# Microcontroller_board_Photodiode_plate.net
KiCad netlist of a schematic drawn in EasyEDA
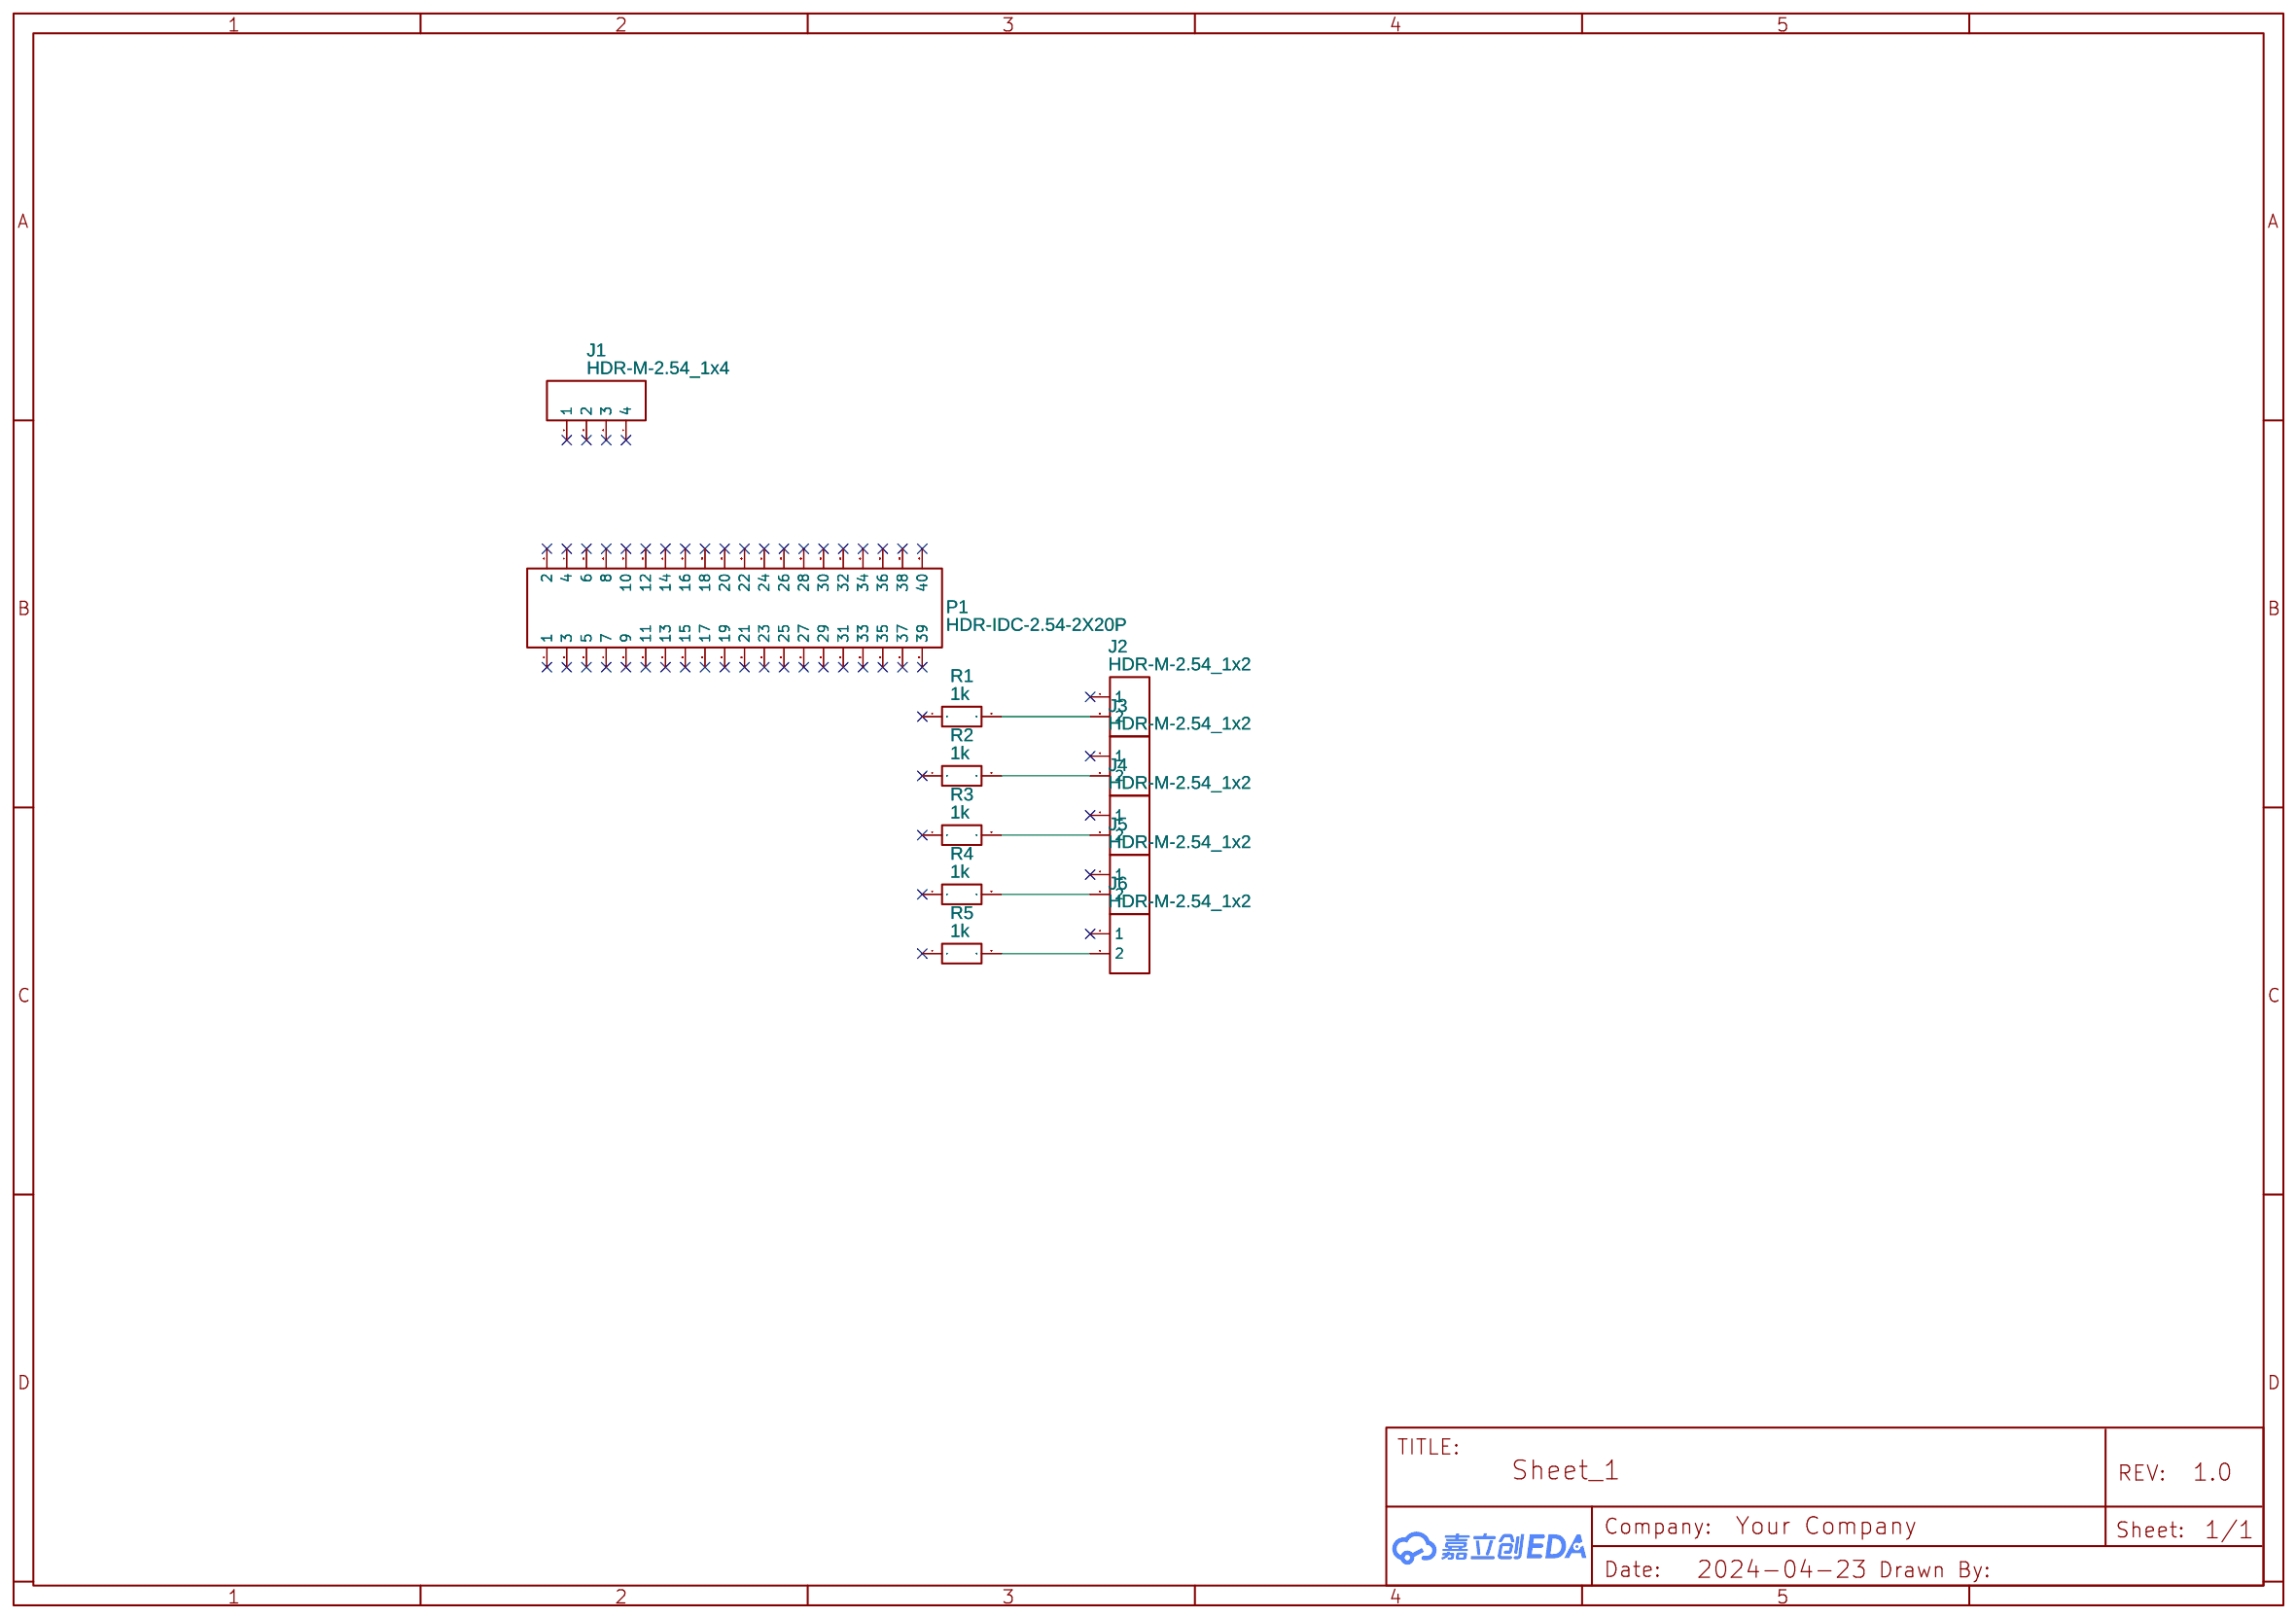
[diagram p0: schematic sheet]

(export (version "E")
  (design (tool "Eeschema 10.0.6"))
  (components
    (comp (ref "J1")
      (value "HDR-M-2.54_1x4")
      (fields (field (name "BOM_Supplier Part") "C124378"))
      (libsource (lib "") (part "HDR-M-2.54_1x4"))
    )
    (comp (ref "J2")
      (value "HDR-M-2.54_1x2")
      (fields (field (name "BOM_Supplier Part") "C124375"))
      (libsource (lib "") (part "HDR-M-2.54_1x2"))
    )
    (comp (ref "J3")
      (value "HDR-M-2.54_1x2")
      (fields (field (name "BOM_Supplier Part") "C124375"))
      (libsource (lib "") (part "HDR-M-2.54_1x2"))
    )
    (comp (ref "J4")
      (value "HDR-M-2.54_1x2")
      (fields (field (name "BOM_Supplier Part") "C124375"))
      (libsource (lib "") (part "HDR-M-2.54_1x2"))
    )
    (comp (ref "J5")
      (value "HDR-M-2.54_1x2")
      (fields (field (name "BOM_Supplier Part") "C124375"))
      (libsource (lib "") (part "HDR-M-2.54_1x2"))
    )
    (comp (ref "J6")
      (value "HDR-M-2.54_1x2")
      (fields (field (name "BOM_Supplier Part") "C124375"))
      (libsource (lib "") (part "HDR-M-2.54_1x2"))
    )
    (comp (ref "P1")
      (value "HDR-IDC-2.54-2X20P")
      (fields
        (field (name "BOM_Manufacturer Part") "IDC Box 2X20 2.54MM")
        (field (name "BOM_Supplier Part") "C9138")
      )
      (libsource (lib "") (part "HDR-IDC-2.54-2X20P"))
    )
    (comp (ref "R1") (value "1k") (libsource (lib "") (part "R_0805_EU")))
    (comp (ref "R2") (value "1k") (libsource (lib "") (part "R_0805_EU")))
    (comp (ref "R3") (value "1k") (libsource (lib "") (part "R_0805_EU")))
    (comp (ref "R4") (value "1k") (libsource (lib "") (part "R_0805_EU")))
    (comp (ref "R5") (value "1k") (libsource (lib "") (part "R_0805_EU")))
  )
  (nets
    (net (code "1") (name "Net-(J2-Pad2)") (class "Default")
      (node (ref "J2") (pin "2") (pinfunction "2_2") (pintype "unspecified"))
      (node (ref "R1") (pin "2") (pinfunction "2_2") (pintype "unspecified"))
    )
    (net (code "2") (name "Net-(J3-Pad2)") (class "Default")
      (node (ref "J3") (pin "2") (pinfunction "2_2") (pintype "unspecified"))
      (node (ref "R2") (pin "2") (pinfunction "2_2") (pintype "unspecified"))
    )
    (net (code "3") (name "Net-(J4-Pad2)") (class "Default")
      (node (ref "J4") (pin "2") (pinfunction "2_2") (pintype "unspecified"))
      (node (ref "R3") (pin "2") (pinfunction "2_2") (pintype "unspecified"))
    )
    (net (code "4") (name "Net-(J5-Pad2)") (class "Default")
      (node (ref "J5") (pin "2") (pinfunction "2_2") (pintype "unspecified"))
      (node (ref "R4") (pin "2") (pinfunction "2_2") (pintype "unspecified"))
    )
    (net (code "5") (name "Net-(J6-Pad2)") (class "Default")
      (node (ref "J6") (pin "2") (pinfunction "2_2") (pintype "unspecified"))
      (node (ref "R5") (pin "2") (pinfunction "2_2") (pintype "unspecified"))
    )
    (net (code "6") (name "unconnected-(J1-Pad1)") (class "Default")
      (node (ref "J1") (pin "1") (pinfunction "1_1") (pintype "unspecified+no_connect"))
    )
    (net (code "7") (name "unconnected-(J1-Pad2)") (class "Default")
      (node (ref "J1") (pin "2") (pinfunction "2_2") (pintype "unspecified+no_connect"))
    )
    (net (code "8") (name "unconnected-(J1-Pad3)") (class "Default")
      (node (ref "J1") (pin "3") (pinfunction "3_3") (pintype "unspecified+no_connect"))
    )
    (net (code "9") (name "unconnected-(J1-Pad4)") (class "Default")
      (node (ref "J1") (pin "4") (pinfunction "4_4") (pintype "unspecified+no_connect"))
    )
    (net (code "10") (name "unconnected-(J2-Pad1)") (class "Default")
      (node (ref "J2") (pin "1") (pinfunction "1_1") (pintype "unspecified+no_connect"))
    )
    (net (code "11") (name "unconnected-(J3-Pad1)") (class "Default")
      (node (ref "J3") (pin "1") (pinfunction "1_1") (pintype "unspecified+no_connect"))
    )
    (net (code "12") (name "unconnected-(J4-Pad1)") (class "Default")
      (node (ref "J4") (pin "1") (pinfunction "1_1") (pintype "unspecified+no_connect"))
    )
    (net (code "13") (name "unconnected-(J5-Pad1)") (class "Default")
      (node (ref "J5") (pin "1") (pinfunction "1_1") (pintype "unspecified+no_connect"))
    )
    (net (code "14") (name "unconnected-(J6-Pad1)") (class "Default")
      (node (ref "J6") (pin "1") (pinfunction "1_1") (pintype "unspecified+no_connect"))
    )
    (net (code "15") (name "unconnected-(P1-Pad1)") (class "Default")
      (node (ref "P1") (pin "1") (pinfunction "1_1") (pintype "unspecified+no_connect"))
    )
    (net (code "16") (name "unconnected-(P1-Pad2)") (class "Default")
      (node (ref "P1") (pin "2") (pinfunction "2_2") (pintype "unspecified+no_connect"))
    )
    (net (code "17") (name "unconnected-(P1-Pad3)") (class "Default")
      (node (ref "P1") (pin "3") (pinfunction "3_3") (pintype "unspecified+no_connect"))
    )
    (net (code "18") (name "unconnected-(P1-Pad4)") (class "Default")
      (node (ref "P1") (pin "4") (pinfunction "4_4") (pintype "unspecified+no_connect"))
    )
    (net (code "19") (name "unconnected-(P1-Pad5)") (class "Default")
      (node (ref "P1") (pin "5") (pinfunction "5_5") (pintype "unspecified+no_connect"))
    )
    (net (code "20") (name "unconnected-(P1-Pad6)") (class "Default")
      (node (ref "P1") (pin "6") (pinfunction "6_6") (pintype "unspecified+no_connect"))
    )
    (net (code "21") (name "unconnected-(P1-Pad7)") (class "Default")
      (node (ref "P1") (pin "7") (pinfunction "7_7") (pintype "unspecified+no_connect"))
    )
    (net (code "22") (name "unconnected-(P1-Pad8)") (class "Default")
      (node (ref "P1") (pin "8") (pinfunction "8_8") (pintype "unspecified+no_connect"))
    )
    (net (code "23") (name "unconnected-(P1-Pad9)") (class "Default")
      (node (ref "P1") (pin "9") (pinfunction "9_9") (pintype "unspecified+no_connect"))
    )
    (net (code "24") (name "unconnected-(P1-Pad10)") (class "Default")
      (node (ref "P1") (pin "10") (pinfunction "10_10") (pintype "unspecified+no_connect"))
    )
    (net (code "25") (name "unconnected-(P1-Pad11)") (class "Default")
      (node (ref "P1") (pin "11") (pinfunction "11_11") (pintype "unspecified+no_connect"))
    )
    (net (code "26") (name "unconnected-(P1-Pad12)") (class "Default")
      (node (ref "P1") (pin "12") (pinfunction "12_12") (pintype "unspecified+no_connect"))
    )
    (net (code "27") (name "unconnected-(P1-Pad13)") (class "Default")
      (node (ref "P1") (pin "13") (pinfunction "13_13") (pintype "unspecified+no_connect"))
    )
    (net (code "28") (name "unconnected-(P1-Pad14)") (class "Default")
      (node (ref "P1") (pin "14") (pinfunction "14_14") (pintype "unspecified+no_connect"))
    )
    (net (code "29") (name "unconnected-(P1-Pad15)") (class "Default")
      (node (ref "P1") (pin "15") (pinfunction "15_15") (pintype "unspecified+no_connect"))
    )
    (net (code "30") (name "unconnected-(P1-Pad16)") (class "Default")
      (node (ref "P1") (pin "16") (pinfunction "16_16") (pintype "unspecified+no_connect"))
    )
    (net (code "31") (name "unconnected-(P1-Pad17)") (class "Default")
      (node (ref "P1") (pin "17") (pinfunction "17_17") (pintype "unspecified+no_connect"))
    )
    (net (code "32") (name "unconnected-(P1-Pad18)") (class "Default")
      (node (ref "P1") (pin "18") (pinfunction "18_18") (pintype "unspecified+no_connect"))
    )
    (net (code "33") (name "unconnected-(P1-Pad19)") (class "Default")
      (node (ref "P1") (pin "19") (pinfunction "19_19") (pintype "unspecified+no_connect"))
    )
    (net (code "34") (name "unconnected-(P1-Pad20)") (class "Default")
      (node (ref "P1") (pin "20") (pinfunction "20_20") (pintype "unspecified+no_connect"))
    )
    (net (code "35") (name "unconnected-(P1-Pad21)") (class "Default")
      (node (ref "P1") (pin "21") (pinfunction "21_21") (pintype "unspecified+no_connect"))
    )
    (net (code "36") (name "unconnected-(P1-Pad22)") (class "Default")
      (node (ref "P1") (pin "22") (pinfunction "22_22") (pintype "unspecified+no_connect"))
    )
    (net (code "37") (name "unconnected-(P1-Pad23)") (class "Default")
      (node (ref "P1") (pin "23") (pinfunction "23_23") (pintype "unspecified+no_connect"))
    )
    (net (code "38") (name "unconnected-(P1-Pad24)") (class "Default")
      (node (ref "P1") (pin "24") (pinfunction "24_24") (pintype "unspecified+no_connect"))
    )
    (net (code "39") (name "unconnected-(P1-Pad25)") (class "Default")
      (node (ref "P1") (pin "25") (pinfunction "25_25") (pintype "unspecified+no_connect"))
    )
    (net (code "40") (name "unconnected-(P1-Pad26)") (class "Default")
      (node (ref "P1") (pin "26") (pinfunction "26_26") (pintype "unspecified+no_connect"))
    )
    (net (code "41") (name "unconnected-(P1-Pad27)") (class "Default")
      (node (ref "P1") (pin "27") (pinfunction "27_27") (pintype "unspecified+no_connect"))
    )
    (net (code "42") (name "unconnected-(P1-Pad28)") (class "Default")
      (node (ref "P1") (pin "28") (pinfunction "28_28") (pintype "unspecified+no_connect"))
    )
    (net (code "43") (name "unconnected-(P1-Pad29)") (class "Default")
      (node (ref "P1") (pin "29") (pinfunction "29_29") (pintype "unspecified+no_connect"))
    )
    (net (code "44") (name "unconnected-(P1-Pad30)") (class "Default")
      (node (ref "P1") (pin "30") (pinfunction "30_30") (pintype "unspecified+no_connect"))
    )
    (net (code "45") (name "unconnected-(P1-Pad31)") (class "Default")
      (node (ref "P1") (pin "31") (pinfunction "31_31") (pintype "unspecified+no_connect"))
    )
    (net (code "46") (name "unconnected-(P1-Pad32)") (class "Default")
      (node (ref "P1") (pin "32") (pinfunction "32_32") (pintype "unspecified+no_connect"))
    )
    (net (code "47") (name "unconnected-(P1-Pad33)") (class "Default")
      (node (ref "P1") (pin "33") (pinfunction "33_33") (pintype "unspecified+no_connect"))
    )
    (net (code "48") (name "unconnected-(P1-Pad34)") (class "Default")
      (node (ref "P1") (pin "34") (pinfunction "34_34") (pintype "unspecified+no_connect"))
    )
    (net (code "49") (name "unconnected-(P1-Pad35)") (class "Default")
      (node (ref "P1") (pin "35") (pinfunction "35_35") (pintype "unspecified+no_connect"))
    )
    (net (code "50") (name "unconnected-(P1-Pad36)") (class "Default")
      (node (ref "P1") (pin "36") (pinfunction "36_36") (pintype "unspecified+no_connect"))
    )
    (net (code "51") (name "unconnected-(P1-Pad37)") (class "Default")
      (node (ref "P1") (pin "37") (pinfunction "37_37") (pintype "unspecified+no_connect"))
    )
    (net (code "52") (name "unconnected-(P1-Pad38)") (class "Default")
      (node (ref "P1") (pin "38") (pinfunction "38_38") (pintype "unspecified+no_connect"))
    )
    (net (code "53") (name "unconnected-(P1-Pad39)") (class "Default")
      (node (ref "P1") (pin "39") (pinfunction "39_39") (pintype "unspecified+no_connect"))
    )
    (net (code "54") (name "unconnected-(P1-Pad40)") (class "Default")
      (node (ref "P1") (pin "40") (pinfunction "40_40") (pintype "unspecified+no_connect"))
    )
    (net (code "55") (name "unconnected-(R1-Pad1)") (class "Default")
      (node (ref "R1") (pin "1") (pinfunction "1_1") (pintype "unspecified+no_connect"))
    )
    (net (code "56") (name "unconnected-(R2-Pad1)") (class "Default")
      (node (ref "R2") (pin "1") (pinfunction "1_1") (pintype "unspecified+no_connect"))
    )
    (net (code "57") (name "unconnected-(R3-Pad1)") (class "Default")
      (node (ref "R3") (pin "1") (pinfunction "1_1") (pintype "unspecified+no_connect"))
    )
    (net (code "58") (name "unconnected-(R4-Pad1)") (class "Default")
      (node (ref "R4") (pin "1") (pinfunction "1_1") (pintype "unspecified+no_connect"))
    )
    (net (code "59") (name "unconnected-(R5-Pad1)") (class "Default")
      (node (ref "R5") (pin "1") (pinfunction "1_1") (pintype "unspecified+no_connect"))
    )
  )
)
